# charlieplate4.net
KiCad netlist of a schematic drawn in EAGLE
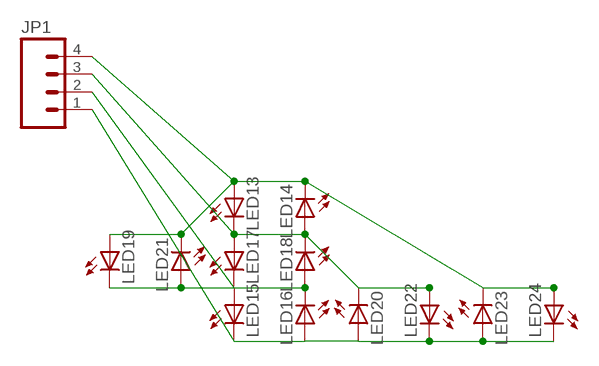
[diagram p0: schematic, sheet 1]

(export (version "E")
  (design (tool "Eeschema 10.0.6"))
  (components
    (comp (ref "JP1")
      (value "M04PTH")
      (footprint "eagle-import:1X04")
      (libsource (lib "eagle-import") (part "M04PTH"))
    )
    (comp (ref "LED13")
      (value "LED3MM")
      (footprint "eagle-import:LED3MM")
      (libsource (lib "eagle-import") (part "LED3MM"))
    )
    (comp (ref "LED14")
      (value "LED3MM")
      (footprint "eagle-import:LED3MM")
      (libsource (lib "eagle-import") (part "LED3MM"))
    )
    (comp (ref "LED15")
      (value "LED3MM")
      (footprint "eagle-import:LED3MM")
      (libsource (lib "eagle-import") (part "LED3MM"))
    )
    (comp (ref "LED16")
      (value "LED3MM")
      (footprint "eagle-import:LED3MM")
      (libsource (lib "eagle-import") (part "LED3MM"))
    )
    (comp (ref "LED17")
      (value "LED3MM")
      (footprint "eagle-import:LED3MM")
      (libsource (lib "eagle-import") (part "LED3MM"))
    )
    (comp (ref "LED18")
      (value "LED3MM")
      (footprint "eagle-import:LED3MM")
      (libsource (lib "eagle-import") (part "LED3MM"))
    )
    (comp (ref "LED19")
      (value "LED3MM")
      (footprint "eagle-import:LED3MM")
      (libsource (lib "eagle-import") (part "LED3MM"))
    )
    (comp (ref "LED20")
      (value "LED3MM")
      (footprint "eagle-import:LED3MM")
      (libsource (lib "eagle-import") (part "LED3MM"))
    )
    (comp (ref "LED21")
      (value "LED3MM")
      (footprint "eagle-import:LED3MM")
      (libsource (lib "eagle-import") (part "LED3MM"))
    )
    (comp (ref "LED22")
      (value "LED3MM")
      (footprint "eagle-import:LED3MM")
      (libsource (lib "eagle-import") (part "LED3MM"))
    )
    (comp (ref "LED23")
      (value "LED3MM")
      (footprint "eagle-import:LED3MM")
      (libsource (lib "eagle-import") (part "LED3MM"))
    )
    (comp (ref "LED24")
      (value "LED3MM")
      (footprint "eagle-import:LED3MM")
      (libsource (lib "eagle-import") (part "LED3MM"))
    )
  )
  (nets
    (net (code "1") (name "Net-(LED13-C)") (class "Default")
      (node (ref "JP1") (pin "3") (pinfunction "3_3") (pintype "passive"))
      (node (ref "LED13") (pin "K") (pinfunction "C_K") (pintype "passive"))
      (node (ref "LED14") (pin "A") (pinfunction "A_A") (pintype "passive"))
      (node (ref "LED17") (pin "A") (pinfunction "A_A") (pintype "passive"))
      (node (ref "LED18") (pin "K") (pinfunction "C_K") (pintype "passive"))
      (node (ref "LED20") (pin "K") (pinfunction "C_K") (pintype "passive"))
      (node (ref "LED22") (pin "A") (pinfunction "A_A") (pintype "passive"))
    )
    (net (code "2") (name "Net-(LED14-C)") (class "Default")
      (node (ref "JP1") (pin "4") (pinfunction "4_4") (pintype "passive"))
      (node (ref "LED13") (pin "A") (pinfunction "A_A") (pintype "passive"))
      (node (ref "LED14") (pin "K") (pinfunction "C_K") (pintype "passive"))
      (node (ref "LED19") (pin "A") (pinfunction "A_A") (pintype "passive"))
      (node (ref "LED21") (pin "K") (pinfunction "C_K") (pintype "passive"))
      (node (ref "LED23") (pin "K") (pinfunction "C_K") (pintype "passive"))
      (node (ref "LED24") (pin "A") (pinfunction "A_A") (pintype "passive"))
    )
    (net (code "3") (name "Net-(LED15-C)") (class "Default")
      (node (ref "JP1") (pin "1") (pinfunction "1_1") (pintype "passive"))
      (node (ref "LED15") (pin "K") (pinfunction "C_K") (pintype "passive"))
      (node (ref "LED16") (pin "A") (pinfunction "A_A") (pintype "passive"))
      (node (ref "LED20") (pin "A") (pinfunction "A_A") (pintype "passive"))
      (node (ref "LED22") (pin "K") (pinfunction "C_K") (pintype "passive"))
      (node (ref "LED23") (pin "A") (pinfunction "A_A") (pintype "passive"))
      (node (ref "LED24") (pin "K") (pinfunction "C_K") (pintype "passive"))
    )
    (net (code "4") (name "Net-(LED16-C)") (class "Default")
      (node (ref "JP1") (pin "2") (pinfunction "2_2") (pintype "passive"))
      (node (ref "LED15") (pin "A") (pinfunction "A_A") (pintype "passive"))
      (node (ref "LED16") (pin "K") (pinfunction "C_K") (pintype "passive"))
      (node (ref "LED17") (pin "K") (pinfunction "C_K") (pintype "passive"))
      (node (ref "LED18") (pin "A") (pinfunction "A_A") (pintype "passive"))
      (node (ref "LED19") (pin "K") (pinfunction "C_K") (pintype "passive"))
      (node (ref "LED21") (pin "A") (pinfunction "A_A") (pintype "passive"))
    )
  )
)
